# Power.net
KiCad netlist of a schematic drawn in Altium Designer
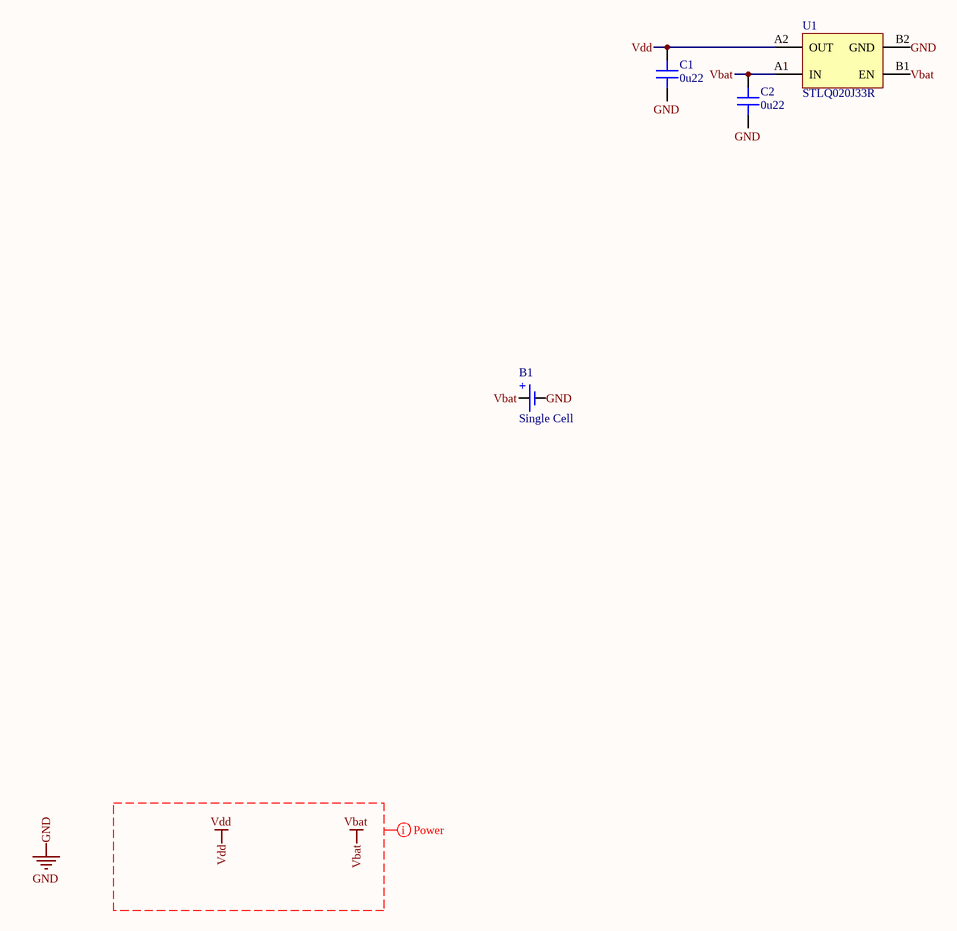
[diagram p0: Power.SchDoc]

(export (version "E")
  (design (tool "Eeschema 10.0.6"))
  (components
    (comp (ref "B1")
      (value "Single Cell")
      (footprint "LINX BAT-HLD-012-SMT")
      (description "CR1216, CR1225 Battery")
      (fields (field (name "PART NUMBER") "BAT-HLD-012-SMT") (field (name "MANUFACTURER") "Linx"))
      (libsource (lib "ekuore-library") (part "Single Cell"))
    )
    (comp (ref "C1")
      (value "0u22")
      (footprint "CAP 0201/0603")
      (description "CAP CER 0201 0.22uF 10V 10% X5R")
      (fields (field (name "PART NUMBER") "GRM033R61A224KE90D") (field (name "MANUFACTURER") "Murata"))
      (libsource (lib "ekuore-library") (part "Capacitor"))
    )
    (comp (ref "C2")
      (value "0u22")
      (footprint "CAP 0201/0603")
      (description "CAP CER 0201 0.22uF 10V 10% X5R")
      (fields (field (name "PART NUMBER") "GRM033R61A224KE90D") (field (name "MANUFACTURER") "Murata"))
      (libsource (lib "ekuore-library") (part "Capacitor"))
    )
    (comp (ref "U1")
      (value "STLQ020J33R")
      (footprint "ST flip-chip4")
      (description "IC REG LIN 3.3V 200MA 4FLIPCHIP")
      (fields (field (name "MANUFACTURER") "STMicroelectronics"))
      (libsource (lib "ekuore-library") (part "STLQ020_flip"))
    )
  )
  (nets
    (net (code "1") (name "GND") (class "Default")
      (node (ref "B1") (pin "2") (pinfunction "-_2") (pintype "passive"))
      (node (ref "C1") (pin "1") (pinfunction "1_1") (pintype "passive"))
      (node (ref "C2") (pin "1") (pinfunction "1_1") (pintype "passive"))
      (node (ref "U1") (pin "B2") (pinfunction "GND_B2") (pintype "passive"))
    )
    (net (code "2") (name "Vbat") (class "Default")
      (node (ref "B1") (pin "1") (pinfunction "+_1") (pintype "passive"))
      (node (ref "C2") (pin "2") (pinfunction "2_2") (pintype "passive"))
      (node (ref "U1") (pin "A1") (pinfunction "IN_A1") (pintype "passive"))
      (node (ref "U1") (pin "B1") (pinfunction "EN_B1") (pintype "passive"))
    )
    (net (code "3") (name "Vdd") (class "Default")
      (node (ref "C1") (pin "2") (pinfunction "2_2") (pintype "passive"))
      (node (ref "U1") (pin "A2") (pinfunction "OUT_A2") (pintype "passive"))
    )
  )
)
